# Nu1_Capsule.net
KiCad netlist of a schematic drawn in EAGLE
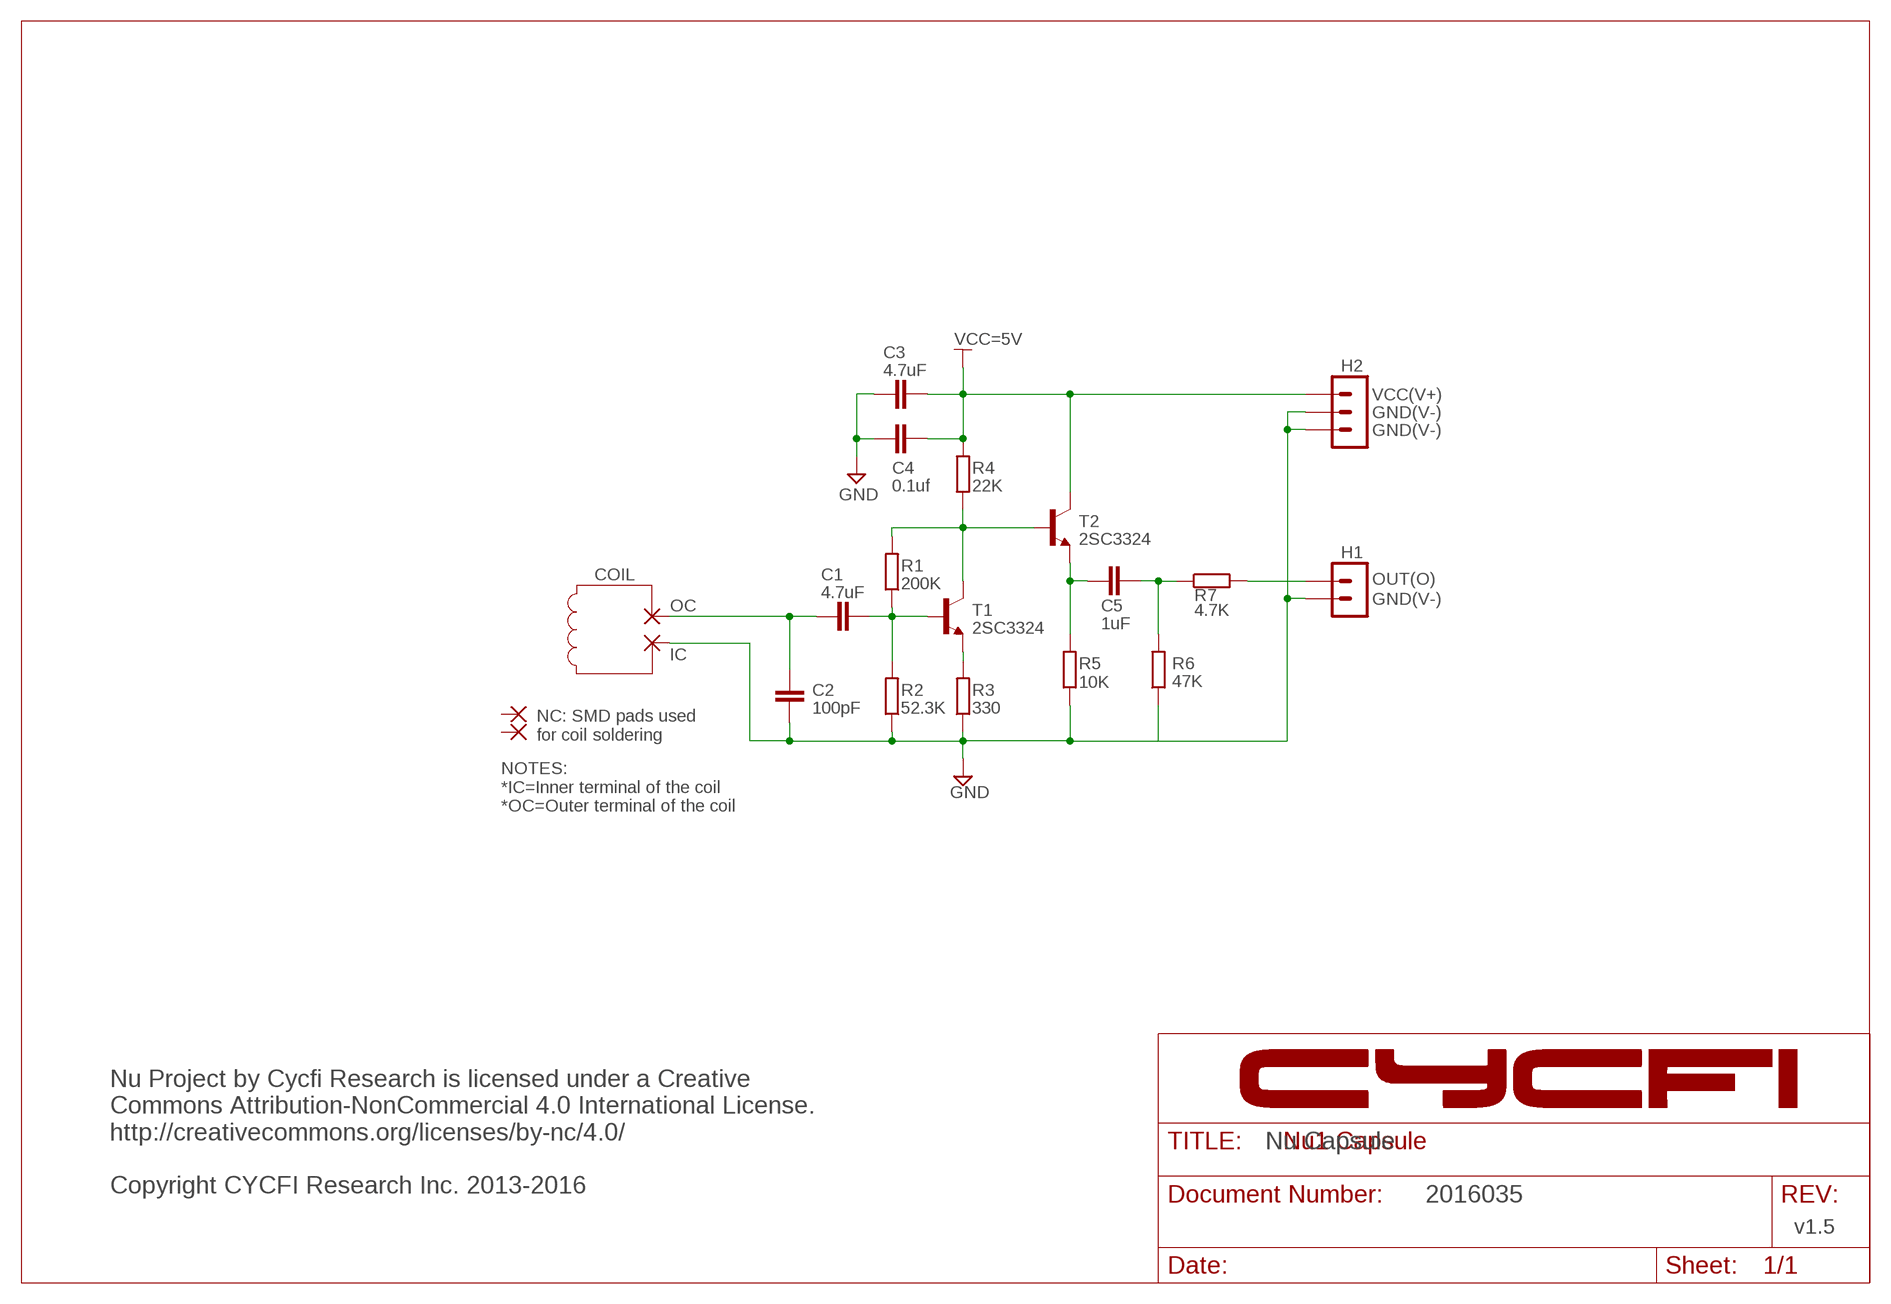
[diagram p0: schematic, sheet 1]

(export (version "E")
  (design (tool "Eeschema 10.0.6"))
  (components
    (comp (ref "C1")
      (value "4.7uF")
      (footprint "eagle-import:C0805")
      (libsource (lib "eagle-import") (part "C-EUC0805"))
    )
    (comp (ref "C2")
      (value "100pF")
      (footprint "eagle-import:C0603")
      (libsource (lib "eagle-import") (part "C-EUC0603"))
    )
    (comp (ref "C3")
      (value "4.7uF")
      (footprint "eagle-import:C0603")
      (libsource (lib "eagle-import") (part "C-EUC0603"))
    )
    (comp (ref "C4")
      (value "0.1uf")
      (footprint "eagle-import:C0603")
      (libsource (lib "eagle-import") (part "C-EUC0603"))
    )
    (comp (ref "C5")
      (value "1uF")
      (footprint "eagle-import:C0805")
      (libsource (lib "eagle-import") (part "C-EUC0805"))
    )
    (comp (ref "H1")
      (value "2P-2MM-TH-MALE")
      (footprint "eagle-import:2P-2MM-TH")
      (libsource (lib "eagle-import") (part "2P-2MM-TH-MALE"))
    )
    (comp (ref "H2")
      (value "3P-2MM-TH-MALE")
      (footprint "eagle-import:3P-2MM-TH")
      (libsource (lib "eagle-import") (part "3P-2MM-TH-MALE"))
    )
    (comp (ref "PAD6")
      (value "WIREPADSMD1,27-254")
      (footprint "eagle-import:SMD1,27-2,54")
      (libsource (lib "eagle-import") (part "WIREPADSMD1,27-254"))
    )
    (comp (ref "PAD7")
      (value "WIREPADSMD1,27-254")
      (footprint "eagle-import:SMD1,27-2,54")
      (libsource (lib "eagle-import") (part "WIREPADSMD1,27-254"))
    )
    (comp (ref "PAD18")
      (value "WIREPADSMD1,27-254")
      (footprint "eagle-import:SMD1,27-2,54")
      (libsource (lib "eagle-import") (part "WIREPADSMD1,27-254"))
    )
    (comp (ref "PAD19")
      (value "WIREPADSMD1,27-254")
      (footprint "eagle-import:SMD1,27-2,54")
      (libsource (lib "eagle-import") (part "WIREPADSMD1,27-254"))
    )
    (comp (ref "R1")
      (value "200K")
      (footprint "eagle-import:R0603")
      (libsource (lib "eagle-import") (part "R-EU_R0603"))
    )
    (comp (ref "R2")
      (value "52.3K")
      (footprint "eagle-import:R0805")
      (libsource (lib "eagle-import") (part "R-EU_R0805"))
    )
    (comp (ref "R3")
      (value "330")
      (footprint "eagle-import:R0402")
      (libsource (lib "eagle-import") (part "R-EU_R0402"))
    )
    (comp (ref "R4")
      (value "22K")
      (footprint "eagle-import:R0402")
      (libsource (lib "eagle-import") (part "R-EU_R0402"))
    )
    (comp (ref "R5")
      (value "10K")
      (footprint "eagle-import:R0402")
      (libsource (lib "eagle-import") (part "R-EU_R0402"))
    )
    (comp (ref "R6")
      (value "47K")
      (footprint "eagle-import:R0402")
      (libsource (lib "eagle-import") (part "R-EU_R0402"))
    )
    (comp (ref "R7")
      (value "4.7K")
      (footprint "eagle-import:R0402")
      (libsource (lib "eagle-import") (part "R-EU_R0402"))
    )
    (comp (ref "T1")
      (value "2SC3324")
      (footprint "eagle-import:SOT23")
      (libsource (lib "eagle-import") (part "BC846"))
    )
    (comp (ref "T2")
      (value "2SC3324")
      (footprint "eagle-import:SOT23")
      (libsource (lib "eagle-import") (part "BC846"))
    )
  )
  (nets
    (net (code "1") (name "GND") (class "Default")
      (node (ref "C2") (pin "1") (pinfunction "1_1") (pintype "passive"))
      (node (ref "C3") (pin "1") (pinfunction "1_1") (pintype "passive"))
      (node (ref "C4") (pin "1") (pinfunction "1_1") (pintype "passive"))
      (node (ref "H1") (pin "P$2") (pinfunction "2_P$2") (pintype "passive"))
      (node (ref "H2") (pin "P$2") (pinfunction "2_P$2") (pintype "passive"))
      (node (ref "H2") (pin "P$3") (pinfunction "3_P$3") (pintype "passive"))
      (node (ref "PAD7") (pin "1") (pinfunction "P_1") (pintype "passive"))
      (node (ref "R2") (pin "1") (pinfunction "1_1") (pintype "passive"))
      (node (ref "R3") (pin "1") (pinfunction "1_1") (pintype "passive"))
      (node (ref "R5") (pin "1") (pinfunction "1_1") (pintype "passive"))
      (node (ref "R6") (pin "1") (pinfunction "1_1") (pintype "passive"))
    )
    (net (code "2") (name "Net-(C5-Pad1)") (class "Default")
      (node (ref "C5") (pin "1") (pinfunction "1_1") (pintype "passive"))
      (node (ref "R6") (pin "2") (pinfunction "2_2") (pintype "passive"))
      (node (ref "R7") (pin "1") (pinfunction "1_1") (pintype "passive"))
    )
    (net (code "3") (name "Net-(H1-1)") (class "Default")
      (node (ref "H1") (pin "P$1") (pinfunction "1_P$1") (pintype "passive"))
      (node (ref "R7") (pin "2") (pinfunction "2_2") (pintype "passive"))
    )
    (net (code "4") (name "Net-(H2-1)") (class "Default")
      (node (ref "C3") (pin "2") (pinfunction "2_2") (pintype "passive"))
      (node (ref "C4") (pin "2") (pinfunction "2_2") (pintype "passive"))
      (node (ref "H2") (pin "P$1") (pinfunction "1_P$1") (pintype "passive"))
      (node (ref "R4") (pin "2") (pinfunction "2_2") (pintype "passive"))
      (node (ref "T2") (pin "3") (pinfunction "C_3") (pintype "passive"))
    )
    (net (code "5") (name "Net-(PAD6-P)") (class "Default")
      (node (ref "C1") (pin "1") (pinfunction "1_1") (pintype "passive"))
      (node (ref "C2") (pin "2") (pinfunction "2_2") (pintype "passive"))
      (node (ref "PAD6") (pin "1") (pinfunction "P_1") (pintype "passive"))
    )
    (net (code "6") (name "Net-(T1-B)") (class "Default")
      (node (ref "C1") (pin "2") (pinfunction "2_2") (pintype "passive"))
      (node (ref "R1") (pin "1") (pinfunction "1_1") (pintype "passive"))
      (node (ref "R2") (pin "2") (pinfunction "2_2") (pintype "passive"))
      (node (ref "T1") (pin "1") (pinfunction "B_1") (pintype "passive"))
    )
    (net (code "7") (name "Net-(T1-C)") (class "Default")
      (node (ref "R1") (pin "2") (pinfunction "2_2") (pintype "passive"))
      (node (ref "R4") (pin "1") (pinfunction "1_1") (pintype "passive"))
      (node (ref "T1") (pin "3") (pinfunction "C_3") (pintype "passive"))
      (node (ref "T2") (pin "1") (pinfunction "B_1") (pintype "passive"))
    )
    (net (code "8") (name "Net-(T1-E)") (class "Default")
      (node (ref "R3") (pin "2") (pinfunction "2_2") (pintype "passive"))
      (node (ref "T1") (pin "2") (pinfunction "E_2") (pintype "passive"))
    )
    (net (code "9") (name "Net-(T2-E)") (class "Default")
      (node (ref "C5") (pin "2") (pinfunction "2_2") (pintype "passive"))
      (node (ref "R5") (pin "2") (pinfunction "2_2") (pintype "passive"))
      (node (ref "T2") (pin "2") (pinfunction "E_2") (pintype "passive"))
    )
    (net (code "10") (name "unconnected-(PAD18-P-Pad1)") (class "Default")
      (node (ref "PAD18") (pin "1") (pinfunction "P_1") (pintype "passive"))
    )
    (net (code "11") (name "unconnected-(PAD19-P-Pad1)") (class "Default")
      (node (ref "PAD19") (pin "1") (pinfunction "P_1") (pintype "passive"))
    )
  )
)
